# Energy.net
KiCad netlist of a schematic drawn in Altium Designer
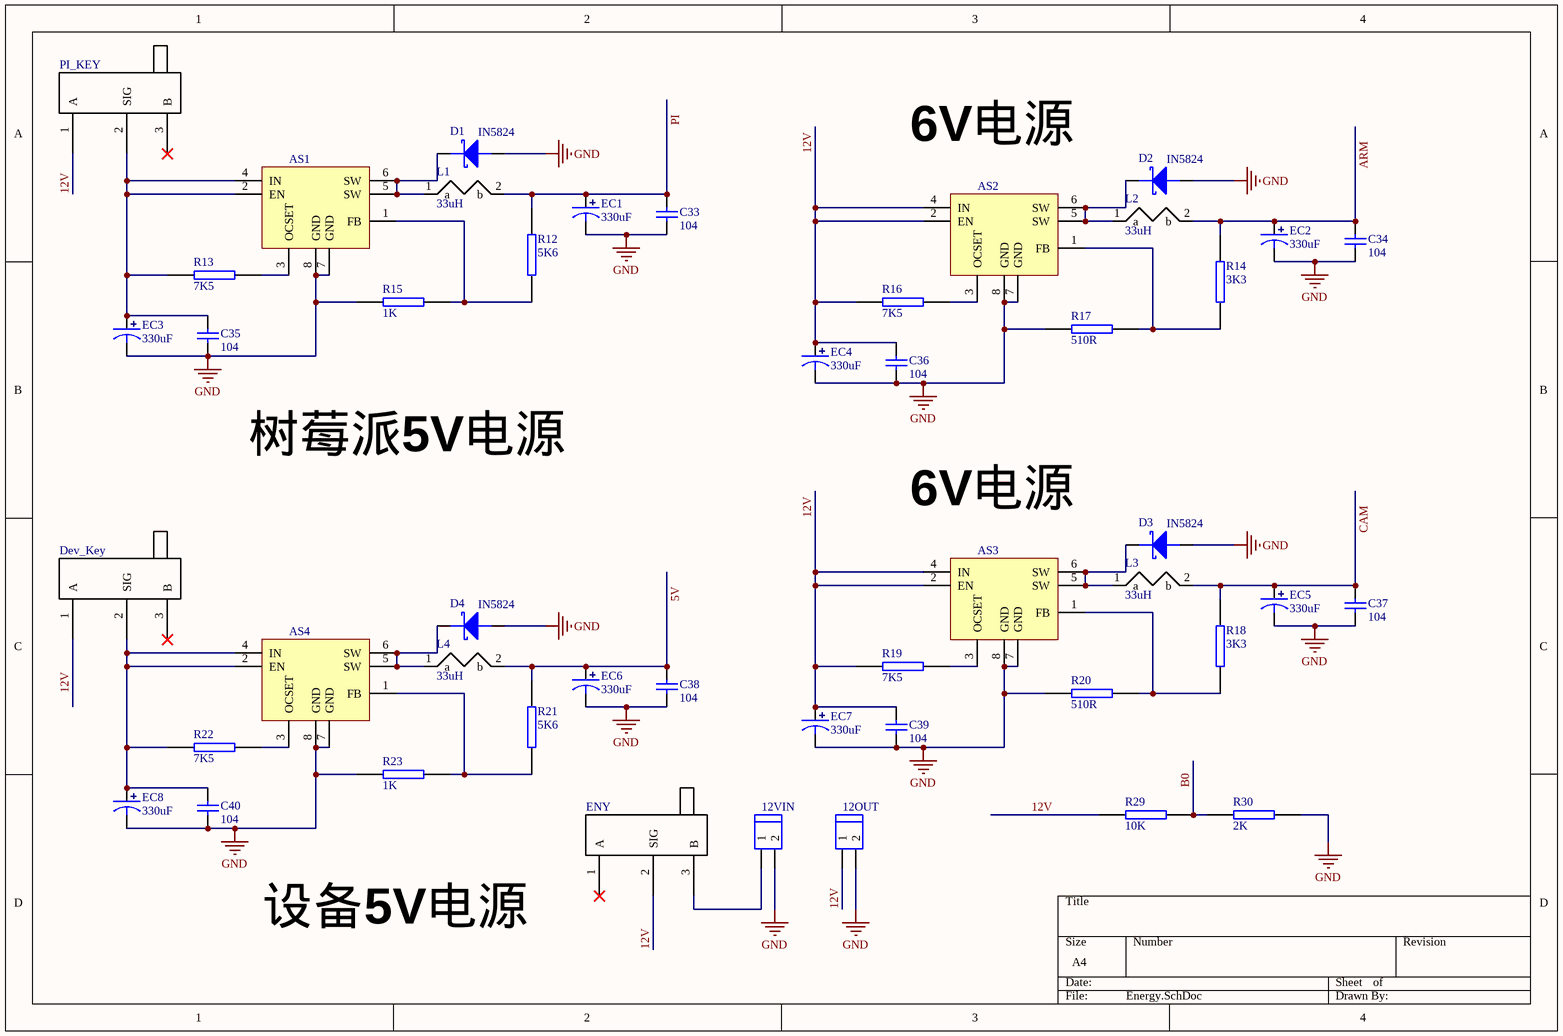
[diagram p0: Energy.SchDoc]

(export (version "E")
  (design (tool "Eeschema 10.0.6"))
  (components
    (comp (ref "12OUT") (value "HEAD2") (footprint "HEAD2L-0.8") (libsource (lib "Robot") (part "HEAD2")))
    (comp (ref "12VIN") (value "HEAD2") (footprint "HEAD2L-0.8") (libsource (lib "Robot") (part "HEAD2")))
    (comp (ref "AS1") (value "U1") (footprint "AS1015") (libsource (lib "输出电压可变直流稳压电源") (part "LED2")))
    (comp (ref "AS2") (value "U1") (footprint "AS1015") (libsource (lib "输出电压可变直流稳压电源") (part "LED2")))
    (comp (ref "AS3") (value "U1") (footprint "AS1015") (libsource (lib "输出电压可变直流稳压电源") (part "LED2")))
    (comp (ref "AS4") (value "U1") (footprint "AS1015") (libsource (lib "输出电压可变直流稳压电源") (part "LED2")))
    (comp (ref "C33")
      (value "Cap")
      (footprint "CAP[0805]")
      (fields (field (name "ALTIUM_UNNAMED_1") "104"))
      (libsource (lib "bob") (part "Cap"))
    )
    (comp (ref "C34")
      (value "Cap")
      (footprint "CAP[0805]")
      (fields (field (name "ALTIUM_UNNAMED_1") "104"))
      (libsource (lib "bob") (part "Cap"))
    )
    (comp (ref "C35")
      (value "Cap")
      (footprint "CAP[0805]")
      (fields (field (name "ALTIUM_UNNAMED_1") "104"))
      (libsource (lib "bob") (part "Cap"))
    )
    (comp (ref "C36")
      (value "Cap")
      (footprint "CAP[0805]")
      (fields (field (name "ALTIUM_UNNAMED_1") "104"))
      (libsource (lib "bob") (part "Cap"))
    )
    (comp (ref "C37")
      (value "Cap")
      (footprint "CAP[0805]")
      (fields (field (name "ALTIUM_UNNAMED_1") "104"))
      (libsource (lib "bob") (part "Cap"))
    )
    (comp (ref "C38")
      (value "Cap")
      (footprint "CAP[0805]")
      (fields (field (name "ALTIUM_UNNAMED_1") "104"))
      (libsource (lib "bob") (part "Cap"))
    )
    (comp (ref "C39")
      (value "Cap")
      (footprint "CAP[0805]")
      (fields (field (name "ALTIUM_UNNAMED_1") "104"))
      (libsource (lib "bob") (part "Cap"))
    )
    (comp (ref "C40")
      (value "Cap")
      (footprint "CAP[0805]")
      (fields (field (name "ALTIUM_UNNAMED_1") "104"))
      (libsource (lib "bob") (part "Cap"))
    )
    (comp (ref "D1")
      (value "IN5824")
      (footprint "SMA/DO-214AC")
      (description "肖特基二极管")
      (libsource (lib "bob") (part "DIODE SCHOTTKY"))
    )
    (comp (ref "D2")
      (value "IN5824")
      (footprint "SMA/DO-214AC")
      (description "肖特基二极管")
      (libsource (lib "bob") (part "DIODE SCHOTTKY"))
    )
    (comp (ref "D3")
      (value "IN5824")
      (footprint "SMA/DO-214AC")
      (description "肖特基二极管")
      (libsource (lib "bob") (part "DIODE SCHOTTKY"))
    )
    (comp (ref "D4")
      (value "IN5824")
      (footprint "SMA/DO-214AC")
      (description "肖特基二极管")
      (libsource (lib "bob") (part "DIODE SCHOTTKY"))
    )
    (comp (ref "Dev_Key") (value "Dev_Key") (footprint "KEY") (libsource (lib "robot2") (part "key")))
    (comp (ref "EC1")
      (value "330uF")
      (footprint "DIP-EC5.0X10X12.5")
      (description "直插电解电容")
      (libsource (lib "bob") (part "DIP_ECAP"))
    )
    (comp (ref "EC2")
      (value "330uF")
      (footprint "DIP-EC5.0X10X12.5")
      (description "直插电解电容")
      (libsource (lib "bob") (part "DIP_ECAP"))
    )
    (comp (ref "EC3")
      (value "330uF")
      (footprint "DIP-EC5.0X10X12.5")
      (description "直插电解电容")
      (libsource (lib "bob") (part "DIP_ECAP"))
    )
    (comp (ref "EC4")
      (value "330uF")
      (footprint "DIP-EC5.0X10X12.5")
      (description "直插电解电容")
      (libsource (lib "bob") (part "DIP_ECAP"))
    )
    (comp (ref "EC5")
      (value "330uF")
      (footprint "DIP-EC5.0X10X12.5")
      (description "直插电解电容")
      (libsource (lib "bob") (part "DIP_ECAP"))
    )
    (comp (ref "EC6")
      (value "330uF")
      (footprint "DIP-EC5.0X10X12.5")
      (description "直插电解电容")
      (libsource (lib "bob") (part "DIP_ECAP"))
    )
    (comp (ref "EC7")
      (value "330uF")
      (footprint "DIP-EC5.0X10X12.5")
      (description "直插电解电容")
      (libsource (lib "bob") (part "DIP_ECAP"))
    )
    (comp (ref "EC8")
      (value "330uF")
      (footprint "DIP-EC5.0X10X12.5")
      (description "直插电解电容")
      (libsource (lib "bob") (part "DIP_ECAP"))
    )
    (comp (ref "ENY") (value "ENY") (footprint "KEY") (libsource (lib "robot2") (part "key")))
    (comp (ref "L1") (value "33uH") (footprint "INDUCTOR") (libsource (lib "robot2") (part "INDUCTOR")))
    (comp (ref "L2") (value "33uH") (footprint "INDUCTOR") (libsource (lib "robot2") (part "INDUCTOR")))
    (comp (ref "L3") (value "33uH") (footprint "INDUCTOR") (libsource (lib "robot2") (part "INDUCTOR")))
    (comp (ref "L4") (value "33uH") (footprint "INDUCTOR") (libsource (lib "robot2") (part "INDUCTOR")))
    (comp (ref "PI_KEY") (value "PI_KEY") (footprint "KEY") (libsource (lib "robot2") (part "key")))
    (comp (ref "R12") (value "5K6") (footprint "R0805") (libsource (lib "bob") (part "RES")))
    (comp (ref "R13") (value "7K5") (footprint "R0805") (libsource (lib "bob") (part "RES")))
    (comp (ref "R14") (value "3K3") (footprint "R0805") (libsource (lib "bob") (part "RES")))
    (comp (ref "R15") (value "1K") (footprint "R0805") (libsource (lib "bob") (part "RES")))
    (comp (ref "R16") (value "7K5") (footprint "R0805") (libsource (lib "bob") (part "RES")))
    (comp (ref "R17") (value "510R") (footprint "R0805") (libsource (lib "bob") (part "RES")))
    (comp (ref "R18") (value "3K3") (footprint "R0805") (libsource (lib "bob") (part "RES")))
    (comp (ref "R19") (value "7K5") (footprint "R0805") (libsource (lib "bob") (part "RES")))
    (comp (ref "R20") (value "510R") (footprint "R0805") (libsource (lib "bob") (part "RES")))
    (comp (ref "R21") (value "5K6") (footprint "R0805") (libsource (lib "bob") (part "RES")))
    (comp (ref "R22") (value "7K5") (footprint "R0805") (libsource (lib "bob") (part "RES")))
    (comp (ref "R23") (value "1K") (footprint "R0805") (libsource (lib "bob") (part "RES")))
    (comp (ref "R29") (value "10K") (footprint "R0805") (libsource (lib "Robot") (part "RES")))
    (comp (ref "R30") (value "2K") (footprint "R0805") (libsource (lib "Robot") (part "RES")))
  )
  (nets
    (net (code "1") (name "/5V") (class "Default")
      (node (ref "C38") (pin "2") (pinfunction "2_2") (pintype "passive"))
      (node (ref "EC6") (pin "1") (pinfunction "1_1") (pintype "passive"))
      (node (ref "L4") (pin "2") (pinfunction "b_2") (pintype "passive"))
      (node (ref "R21") (pin "2") (pinfunction "2_2") (pintype "passive"))
    )
    (net (code "2") (name "/12V") (class "Default")
      (node (ref "12OUT") (pin "1") (pinfunction "1_1") (pintype "passive"))
      (node (ref "AS2") (pin "2") (pinfunction "EN_2") (pintype "passive"))
      (node (ref "AS2") (pin "4") (pinfunction "IN_4") (pintype "passive"))
      (node (ref "AS3") (pin "2") (pinfunction "EN_2") (pintype "passive"))
      (node (ref "AS3") (pin "4") (pinfunction "IN_4") (pintype "passive"))
      (node (ref "C36") (pin "2") (pinfunction "2_2") (pintype "passive"))
      (node (ref "C39") (pin "2") (pinfunction "2_2") (pintype "passive"))
      (node (ref "Dev_Key") (pin "1") (pinfunction "A_1") (pintype "passive"))
      (node (ref "EC4") (pin "1") (pinfunction "1_1") (pintype "passive"))
      (node (ref "EC7") (pin "1") (pinfunction "1_1") (pintype "passive"))
      (node (ref "ENY") (pin "2") (pinfunction "SIG_2") (pintype "passive"))
      (node (ref "PI_KEY") (pin "1") (pinfunction "A_1") (pintype "passive"))
      (node (ref "R16") (pin "1") (pinfunction "1_1") (pintype "passive"))
      (node (ref "R19") (pin "1") (pinfunction "1_1") (pintype "passive"))
      (node (ref "R29") (pin "1") (pinfunction "1_1") (pintype "passive"))
    )
    (net (code "3") (name "/ARM") (class "Default")
      (node (ref "C34") (pin "2") (pinfunction "2_2") (pintype "passive"))
      (node (ref "EC2") (pin "1") (pinfunction "1_1") (pintype "passive"))
      (node (ref "L2") (pin "2") (pinfunction "b_2") (pintype "passive"))
      (node (ref "R14") (pin "2") (pinfunction "2_2") (pintype "passive"))
    )
    (net (code "4") (name "/B0") (class "Default")
      (node (ref "R29") (pin "2") (pinfunction "2_2") (pintype "passive"))
      (node (ref "R30") (pin "1") (pinfunction "1_1") (pintype "passive"))
    )
    (net (code "5") (name "/CAM") (class "Default")
      (node (ref "C37") (pin "2") (pinfunction "2_2") (pintype "passive"))
      (node (ref "EC5") (pin "1") (pinfunction "1_1") (pintype "passive"))
      (node (ref "L3") (pin "2") (pinfunction "b_2") (pintype "passive"))
      (node (ref "R18") (pin "2") (pinfunction "2_2") (pintype "passive"))
    )
    (net (code "6") (name "/PI") (class "Default")
      (node (ref "C33") (pin "2") (pinfunction "2_2") (pintype "passive"))
      (node (ref "EC1") (pin "1") (pinfunction "1_1") (pintype "passive"))
      (node (ref "L1") (pin "2") (pinfunction "b_2") (pintype "passive"))
      (node (ref "R12") (pin "2") (pinfunction "2_2") (pintype "passive"))
    )
    (net (code "7") (name "GND") (class "Default")
      (node (ref "12OUT") (pin "2") (pinfunction "2_2") (pintype "passive"))
      (node (ref "12VIN") (pin "2") (pinfunction "2_2") (pintype "passive"))
      (node (ref "AS1") (pin "7") (pinfunction "GND_7") (pintype "passive"))
      (node (ref "AS1") (pin "8") (pinfunction "GND_8") (pintype "passive"))
      (node (ref "AS2") (pin "7") (pinfunction "GND_7") (pintype "passive"))
      (node (ref "AS2") (pin "8") (pinfunction "GND_8") (pintype "passive"))
      (node (ref "AS3") (pin "7") (pinfunction "GND_7") (pintype "passive"))
      (node (ref "AS3") (pin "8") (pinfunction "GND_8") (pintype "passive"))
      (node (ref "AS4") (pin "7") (pinfunction "GND_7") (pintype "passive"))
      (node (ref "AS4") (pin "8") (pinfunction "GND_8") (pintype "passive"))
      (node (ref "C33") (pin "1") (pinfunction "1_1") (pintype "passive"))
      (node (ref "C34") (pin "1") (pinfunction "1_1") (pintype "passive"))
      (node (ref "C35") (pin "1") (pinfunction "1_1") (pintype "passive"))
      (node (ref "C36") (pin "1") (pinfunction "1_1") (pintype "passive"))
      (node (ref "C37") (pin "1") (pinfunction "1_1") (pintype "passive"))
      (node (ref "C38") (pin "1") (pinfunction "1_1") (pintype "passive"))
      (node (ref "C39") (pin "1") (pinfunction "1_1") (pintype "passive"))
      (node (ref "C40") (pin "1") (pinfunction "1_1") (pintype "passive"))
      (node (ref "D1") (pin "A") (pinfunction "A_A") (pintype "passive"))
      (node (ref "D2") (pin "A") (pinfunction "A_A") (pintype "passive"))
      (node (ref "D3") (pin "A") (pinfunction "A_A") (pintype "passive"))
      (node (ref "D4") (pin "A") (pinfunction "A_A") (pintype "passive"))
      (node (ref "EC1") (pin "2") (pinfunction "2_2") (pintype "passive"))
      (node (ref "EC2") (pin "2") (pinfunction "2_2") (pintype "passive"))
      (node (ref "EC3") (pin "2") (pinfunction "2_2") (pintype "passive"))
      (node (ref "EC4") (pin "2") (pinfunction "2_2") (pintype "passive"))
      (node (ref "EC5") (pin "2") (pinfunction "2_2") (pintype "passive"))
      (node (ref "EC6") (pin "2") (pinfunction "2_2") (pintype "passive"))
      (node (ref "EC7") (pin "2") (pinfunction "2_2") (pintype "passive"))
      (node (ref "EC8") (pin "2") (pinfunction "2_2") (pintype "passive"))
      (node (ref "R15") (pin "2") (pinfunction "2_2") (pintype "passive"))
      (node (ref "R17") (pin "2") (pinfunction "2_2") (pintype "passive"))
      (node (ref "R20") (pin "2") (pinfunction "2_2") (pintype "passive"))
      (node (ref "R23") (pin "2") (pinfunction "2_2") (pintype "passive"))
      (node (ref "R30") (pin "2") (pinfunction "2_2") (pintype "passive"))
    )
    (net (code "8") (name "Net-(AS1-EN)") (class "Default")
      (node (ref "AS1") (pin "2") (pinfunction "EN_2") (pintype "passive"))
      (node (ref "AS1") (pin "4") (pinfunction "IN_4") (pintype "passive"))
      (node (ref "C35") (pin "2") (pinfunction "2_2") (pintype "passive"))
      (node (ref "EC3") (pin "1") (pinfunction "1_1") (pintype "passive"))
      (node (ref "PI_KEY") (pin "2") (pinfunction "SIG_2") (pintype "passive"))
      (node (ref "R13") (pin "1") (pinfunction "1_1") (pintype "passive"))
    )
    (net (code "9") (name "Net-(AS1-FB)") (class "Default")
      (node (ref "AS1") (pin "1") (pinfunction "FB_1") (pintype "passive"))
      (node (ref "R12") (pin "1") (pinfunction "1_1") (pintype "passive"))
      (node (ref "R15") (pin "1") (pinfunction "1_1") (pintype "passive"))
    )
    (net (code "10") (name "Net-(AS1-OCSET)") (class "Default")
      (node (ref "AS1") (pin "3") (pinfunction "OCSET_3") (pintype "passive"))
      (node (ref "R13") (pin "2") (pinfunction "2_2") (pintype "passive"))
    )
    (net (code "11") (name "Net-(AS2-FB)") (class "Default")
      (node (ref "AS2") (pin "1") (pinfunction "FB_1") (pintype "passive"))
      (node (ref "R14") (pin "1") (pinfunction "1_1") (pintype "passive"))
      (node (ref "R17") (pin "1") (pinfunction "1_1") (pintype "passive"))
    )
    (net (code "12") (name "Net-(AS2-OCSET)") (class "Default")
      (node (ref "AS2") (pin "3") (pinfunction "OCSET_3") (pintype "passive"))
      (node (ref "R16") (pin "2") (pinfunction "2_2") (pintype "passive"))
    )
    (net (code "13") (name "Net-(AS3-FB)") (class "Default")
      (node (ref "AS3") (pin "1") (pinfunction "FB_1") (pintype "passive"))
      (node (ref "R18") (pin "1") (pinfunction "1_1") (pintype "passive"))
      (node (ref "R20") (pin "1") (pinfunction "1_1") (pintype "passive"))
    )
    (net (code "14") (name "Net-(AS3-OCSET)") (class "Default")
      (node (ref "AS3") (pin "3") (pinfunction "OCSET_3") (pintype "passive"))
      (node (ref "R19") (pin "2") (pinfunction "2_2") (pintype "passive"))
    )
    (net (code "15") (name "Net-(AS4-EN)") (class "Default")
      (node (ref "AS4") (pin "2") (pinfunction "EN_2") (pintype "passive"))
      (node (ref "AS4") (pin "4") (pinfunction "IN_4") (pintype "passive"))
      (node (ref "C40") (pin "2") (pinfunction "2_2") (pintype "passive"))
      (node (ref "Dev_Key") (pin "2") (pinfunction "SIG_2") (pintype "passive"))
      (node (ref "EC8") (pin "1") (pinfunction "1_1") (pintype "passive"))
      (node (ref "R22") (pin "1") (pinfunction "1_1") (pintype "passive"))
    )
    (net (code "16") (name "Net-(AS4-FB)") (class "Default")
      (node (ref "AS4") (pin "1") (pinfunction "FB_1") (pintype "passive"))
      (node (ref "R21") (pin "1") (pinfunction "1_1") (pintype "passive"))
      (node (ref "R23") (pin "1") (pinfunction "1_1") (pintype "passive"))
    )
    (net (code "17") (name "Net-(AS4-OCSET)") (class "Default")
      (node (ref "AS4") (pin "3") (pinfunction "OCSET_3") (pintype "passive"))
      (node (ref "R22") (pin "2") (pinfunction "2_2") (pintype "passive"))
    )
    (net (code "18") (name "Net-(ENY-B)") (class "Default")
      (node (ref "12VIN") (pin "1") (pinfunction "1_1") (pintype "passive"))
      (node (ref "ENY") (pin "3") (pinfunction "B_3") (pintype "passive"))
    )
    (net (code "19") (name "Net-(L1-a)") (class "Default")
      (node (ref "AS1") (pin "5") (pinfunction "SW_5") (pintype "passive"))
      (node (ref "AS1") (pin "6") (pinfunction "SW_6") (pintype "passive"))
      (node (ref "D1") (pin "K") (pinfunction "K_K") (pintype "passive"))
      (node (ref "L1") (pin "1") (pinfunction "a_1") (pintype "passive"))
    )
    (net (code "20") (name "Net-(L2-a)") (class "Default")
      (node (ref "AS2") (pin "5") (pinfunction "SW_5") (pintype "passive"))
      (node (ref "AS2") (pin "6") (pinfunction "SW_6") (pintype "passive"))
      (node (ref "D2") (pin "K") (pinfunction "K_K") (pintype "passive"))
      (node (ref "L2") (pin "1") (pinfunction "a_1") (pintype "passive"))
    )
    (net (code "21") (name "Net-(L3-a)") (class "Default")
      (node (ref "AS3") (pin "5") (pinfunction "SW_5") (pintype "passive"))
      (node (ref "AS3") (pin "6") (pinfunction "SW_6") (pintype "passive"))
      (node (ref "D3") (pin "K") (pinfunction "K_K") (pintype "passive"))
      (node (ref "L3") (pin "1") (pinfunction "a_1") (pintype "passive"))
    )
    (net (code "22") (name "Net-(L4-a)") (class "Default")
      (node (ref "AS4") (pin "5") (pinfunction "SW_5") (pintype "passive"))
      (node (ref "AS4") (pin "6") (pinfunction "SW_6") (pintype "passive"))
      (node (ref "D4") (pin "K") (pinfunction "K_K") (pintype "passive"))
      (node (ref "L4") (pin "1") (pinfunction "a_1") (pintype "passive"))
    )
    (net (code "23") (name "unconnected-(Dev_Key-B-Pad3)") (class "Default")
      (node (ref "Dev_Key") (pin "3") (pinfunction "B_3") (pintype "passive+no_connect"))
    )
    (net (code "24") (name "unconnected-(ENY-A-Pad1)") (class "Default")
      (node (ref "ENY") (pin "1") (pinfunction "A_1") (pintype "passive+no_connect"))
    )
    (net (code "25") (name "unconnected-(PI_KEY-B-Pad3)") (class "Default")
      (node (ref "PI_KEY") (pin "3") (pinfunction "B_3") (pintype "passive+no_connect"))
    )
  )
)
